# DK-PM-FV-VC-Buck_NonIsolated_V1_0.net
KiCad netlist of a schematic drawn in Altium Designer
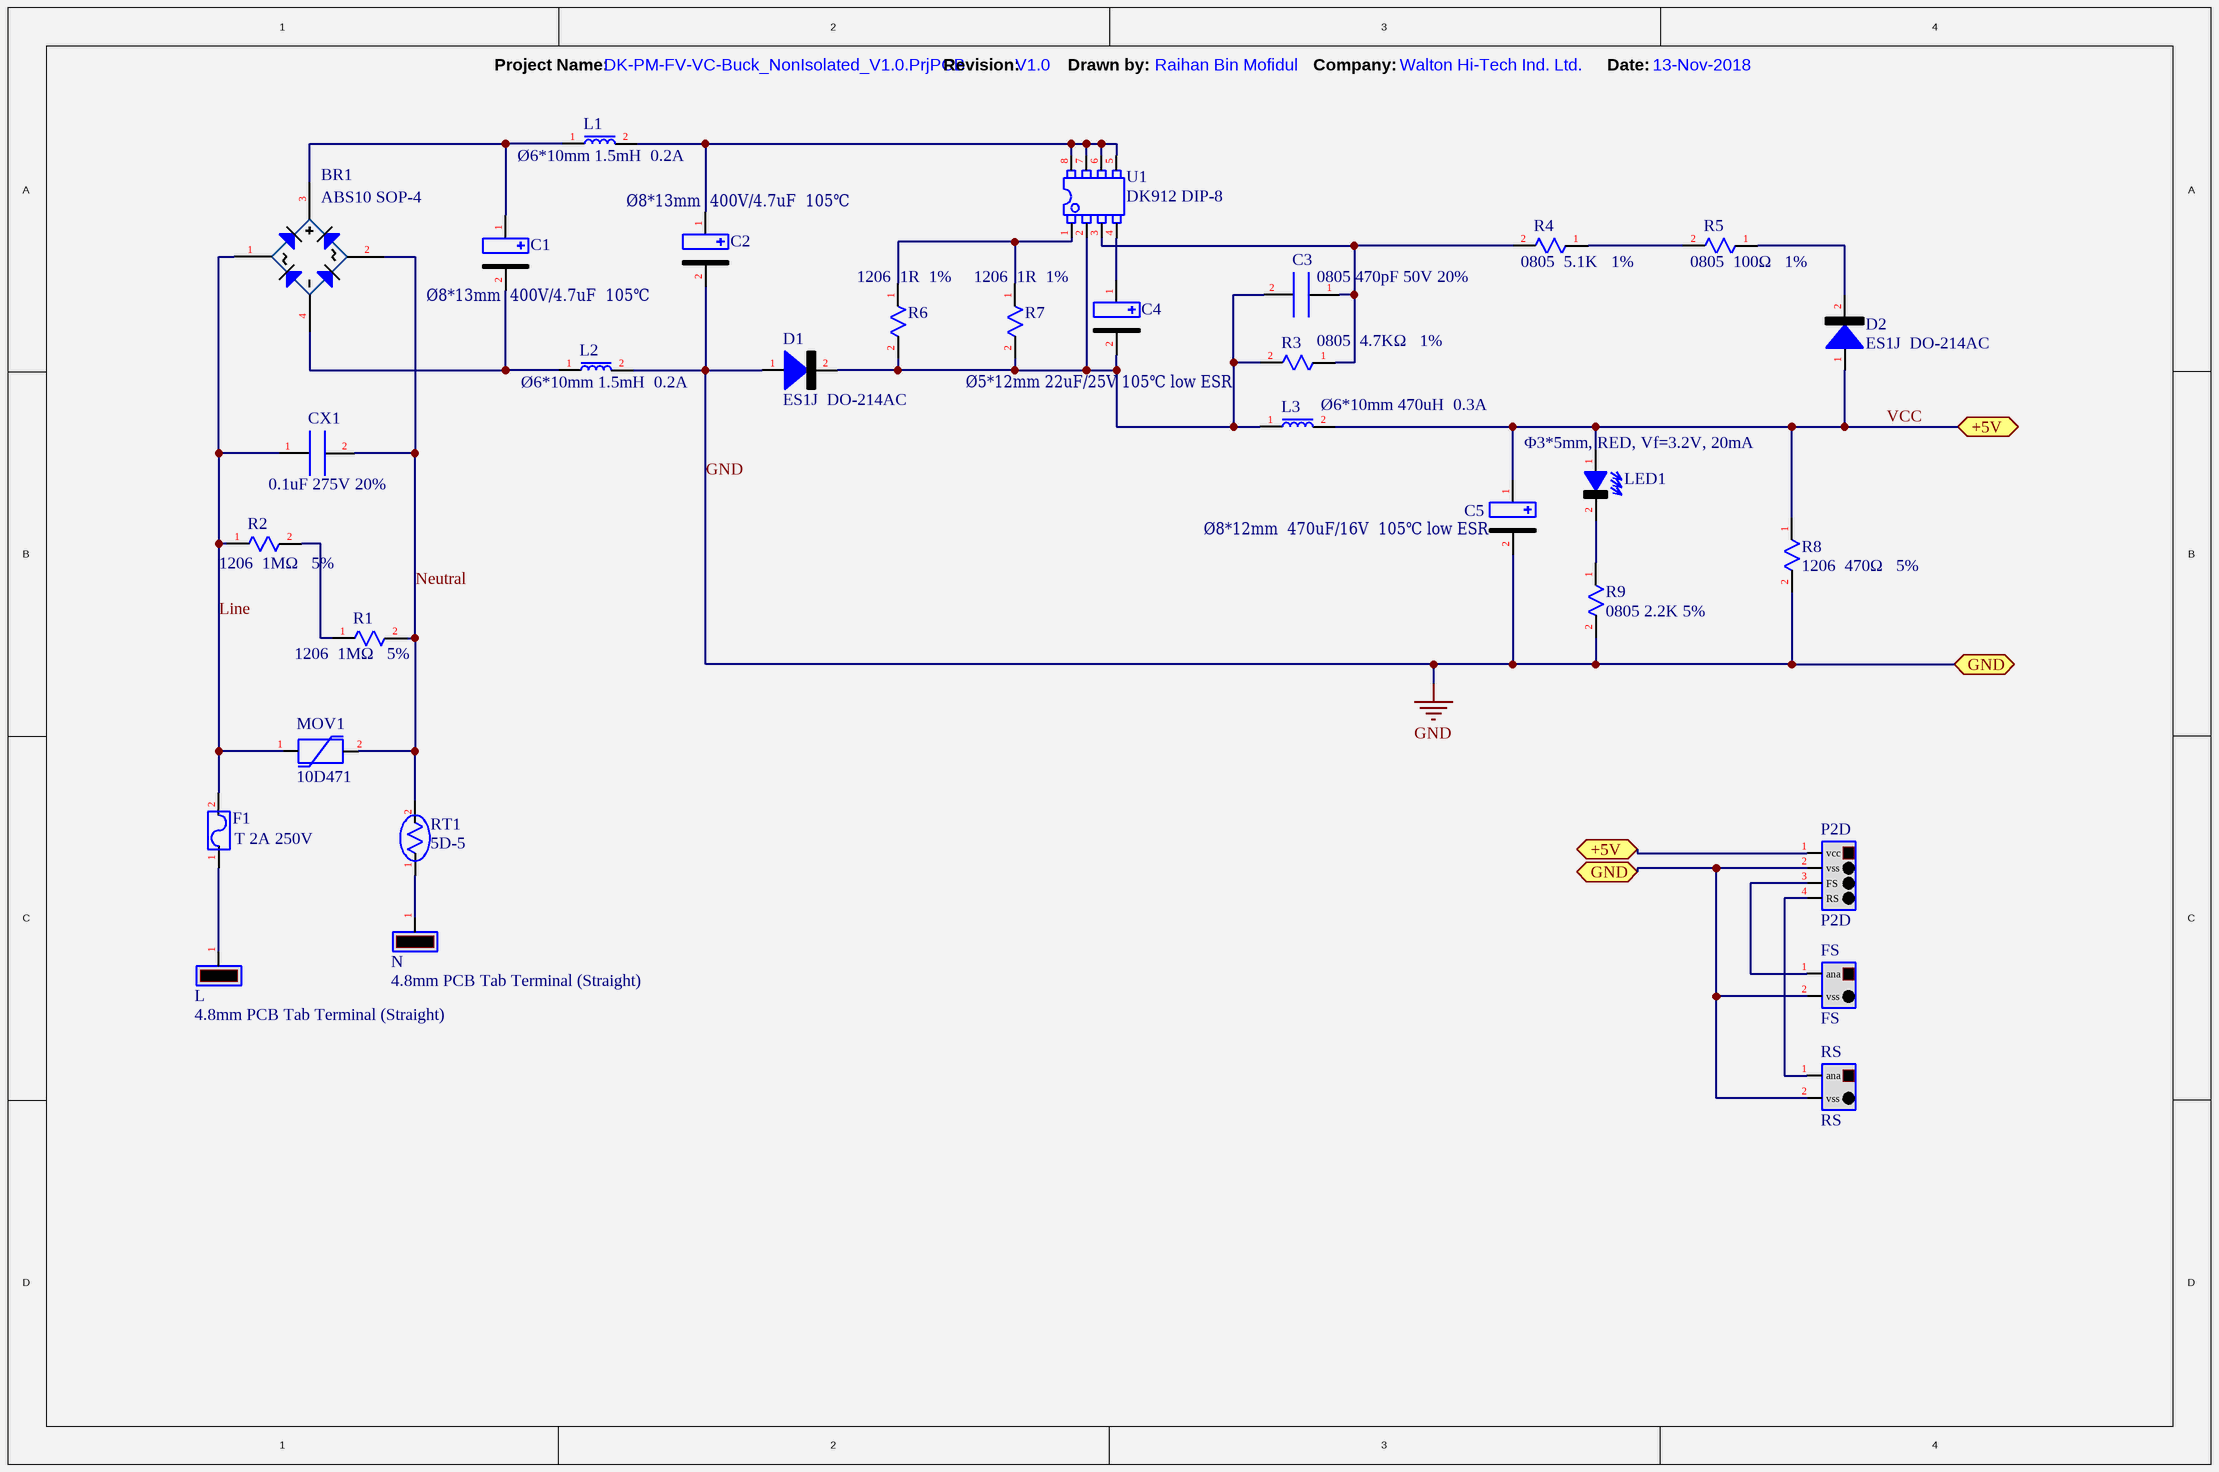
[diagram p0: DK-PM-FV-VC-Buck_NonIsolated_V1.0.SchDoc]

(export (version "E")
  (design (tool "Eeschema 10.0.6"))
  (components
    (comp (ref "BR1")
      (value "ABS10 SOP-4")
      (footprint "BR_SMD_ABS10")
      (libsource (lib "RBM_V1.0_Schlib") (part "Bridge Rectifier"))
    )
    (comp (ref "C1")
      (value "Ø8*13mm  400V/4.7uF  105℃")
      (footprint "C_8x13_P3.556")
      (libsource (lib "RBM_V1.0_Schlib") (part "Capacitor Polar"))
    )
    (comp (ref "C2")
      (value "Ø8*13mm  400V/4.7uF  105℃")
      (footprint "C_8x13_P3.556")
      (libsource (lib "RBM_V1.0_Schlib") (part "Capacitor Polar"))
    )
    (comp (ref "C3")
      (value "0805 470pF 50V 20%")
      (footprint "C_0805")
      (libsource (lib "RBM_V1.0_Schlib") (part "Capacitor Non-Polar"))
    )
    (comp (ref "C4")
      (value "Ø5*12mm 22uF/25V 105℃ low ESR")
      (footprint "C_5x12_P2.54")
      (libsource (lib "RBM_V1.0_Schlib") (part "Capacitor Polar"))
    )
    (comp (ref "C5")
      (value "Ø8*12mm  470uF/16V  105℃ low ESR")
      (footprint "C_8x12_P3.556")
      (libsource (lib "RBM_V1.0_Schlib") (part "Capacitor Polar"))
    )
    (comp (ref "CX1")
      (value "0.1uF 275V 20%")
      (footprint "C_X1_P10")
      (libsource (lib "RBM_V1.0_Schlib") (part "Capacitor Non-Polar"))
    )
    (comp (ref "D1")
      (value "ES1J  DO-214AC")
      (footprint "D_ES1J-DO-214AC")
      (libsource (lib "RBM_V1.0_Schlib") (part "Diode"))
    )
    (comp (ref "D2")
      (value "ES1J  DO-214AC")
      (footprint "D_ES1J-DO-214AC")
      (libsource (lib "RBM_V1.0_Schlib") (part "Diode"))
    )
    (comp (ref "F1")
      (value "T 2A 250V")
      (footprint "F_4x8_P5")
      (libsource (lib "RBM_V1.0_Schlib") (part "Fuse"))
    )
    (comp (ref "FS")
      (value "FS")
      (footprint "CN_B2B-XH-A_RED")
      (libsource (lib "RBM_V1.0_Schlib") (part "Connector_2PINs"))
    )
    (comp (ref "L")
      (value "4.8mm PCB Tab Terminal (Straight)")
      (footprint "CN_4.8mm PCB Tab Terminal (Straight)")
      (libsource (lib "RBM_V1.0_Schlib") (part "Connector_1PIN"))
    )
    (comp (ref "L1")
      (value "Ø6*10mm 1.5mH  0.2A")
      (footprint "L_6x10_P3")
      (libsource (lib "RBM_V1.0_Schlib") (part "Inductor"))
    )
    (comp (ref "L2")
      (value "Ø6*10mm 1.5mH  0.2A")
      (footprint "L_6x10_P3")
      (libsource (lib "RBM_V1.0_Schlib") (part "Inductor"))
    )
    (comp (ref "L3")
      (value "Ø6*10mm 470uH  0.3A")
      (footprint "L_6x10_P3")
      (libsource (lib "RBM_V1.0_Schlib") (part "Inductor"))
    )
    (comp (ref "LED1")
      (value "Φ3*5mm, RED, Vf=3.2V, 20mA")
      (footprint "LED_3x5_P2.5")
      (libsource (lib "RBM_V1.0_Schlib") (part "LED"))
    )
    (comp (ref "MOV1")
      (value "10D471")
      (footprint "MOV_10D471")
      (libsource (lib "RBM_V1.0_Schlib") (part "Varistor"))
    )
    (comp (ref "N")
      (value "4.8mm PCB Tab Terminal (Straight)")
      (footprint "CN_4.8mm PCB Tab Terminal (Straight)")
      (libsource (lib "RBM_V1.0_Schlib") (part "Connector_1PIN"))
    )
    (comp (ref "P2D")
      (value "P2D")
      (footprint "CN_BM04B-GHS-TBT_180_DIP")
      (libsource (lib "RBM_V1.0_Schlib") (part "Connector_4PINs"))
    )
    (comp (ref "R1")
      (value "1206  1MΩ   5%")
      (footprint "R_1206")
      (libsource (lib "RBM_V1.0_Schlib") (part "Resistor"))
    )
    (comp (ref "R2")
      (value "1206  1MΩ   5%")
      (footprint "R_1206")
      (libsource (lib "RBM_V1.0_Schlib") (part "Resistor"))
    )
    (comp (ref "R3")
      (value "0805  4.7KΩ   1%")
      (footprint "R_0805")
      (libsource (lib "RBM_V1.0_Schlib") (part "Resistor"))
    )
    (comp (ref "R4")
      (value "0805  5.1K   1%")
      (footprint "R_0805")
      (libsource (lib "RBM_V1.0_Schlib") (part "Resistor"))
    )
    (comp (ref "R5")
      (value "0805  100Ω   1%")
      (footprint "R_0805")
      (libsource (lib "RBM_V1.0_Schlib") (part "Resistor"))
    )
    (comp (ref "R6")
      (value "1206  1R  1%")
      (footprint "R_1206")
      (libsource (lib "RBM_V1.0_Schlib") (part "Resistor"))
    )
    (comp (ref "R7")
      (value "1206  1R  1%")
      (footprint "R_1206")
      (libsource (lib "RBM_V1.0_Schlib") (part "Resistor"))
    )
    (comp (ref "R8")
      (value "1206  470Ω   5%")
      (footprint "R_1206")
      (libsource (lib "RBM_V1.0_Schlib") (part "Resistor"))
    )
    (comp (ref "R9")
      (value "0805 2.2K 5%")
      (footprint "R_0805")
      (libsource (lib "RBM_V1.0_Schlib") (part "Resistor"))
    )
    (comp (ref "RS")
      (value "RS")
      (footprint "CN_B2B-XH-A_WHITE")
      (libsource (lib "RBM_V1.0_Schlib") (part "Connector_2PINs"))
    )
    (comp (ref "RT1")
      (value "5D-5")
      (footprint "RT_5D-5-(B)")
      (libsource (lib "RBM_V1.0_Schlib") (part "Thermistor"))
    )
    (comp (ref "U1")
      (value "DK912 DIP-8")
      (footprint "U_DK912_TH")
      (libsource (lib "RBM_V1.0_Schlib") (part "IC_SMPS_8pin"))
    )
  )
  (nets
    (net (code "1") (name "/Line") (class "Default")
      (node (ref "BR1") (pin "1") (pinfunction "AC_1") (pintype "passive"))
      (node (ref "CX1") (pin "1") (pinfunction "1_1") (pintype "passive"))
      (node (ref "F1") (pin "2") (pinfunction "2_2") (pintype "passive"))
      (node (ref "MOV1") (pin "1") (pinfunction "1_1") (pintype "passive"))
      (node (ref "R2") (pin "1") (pinfunction "1_1") (pintype "passive"))
    )
    (net (code "2") (name "/Neutral") (class "Default")
      (node (ref "BR1") (pin "2") (pinfunction "AC_2") (pintype "passive"))
      (node (ref "CX1") (pin "2") (pinfunction "2_2") (pintype "passive"))
      (node (ref "MOV1") (pin "2") (pinfunction "2_2") (pintype "passive"))
      (node (ref "R1") (pin "2") (pinfunction "2_2") (pintype "passive"))
      (node (ref "RT1") (pin "2") (pinfunction "2_2") (pintype "passive"))
    )
    (net (code "3") (name "/VCC") (class "Default")
      (node (ref "C5") (pin "1") (pinfunction "vdd_1") (pintype "passive"))
      (node (ref "D2") (pin "1") (pinfunction "vdd_1") (pintype "passive"))
      (node (ref "L3") (pin "2") (pinfunction "2_2") (pintype "passive"))
      (node (ref "LED1") (pin "1") (pinfunction "vdd_1") (pintype "passive"))
      (node (ref "P2D") (pin "1") (pinfunction "vcc_1") (pintype "passive"))
      (node (ref "R8") (pin "1") (pinfunction "1_1") (pintype "passive"))
    )
    (net (code "4") (name "GND") (class "Default")
      (node (ref "C2") (pin "2") (pinfunction "vss_2") (pintype "passive"))
      (node (ref "C5") (pin "2") (pinfunction "vss_2") (pintype "passive"))
      (node (ref "D1") (pin "1") (pinfunction "vdd_1") (pintype "passive"))
      (node (ref "FS") (pin "2") (pinfunction "vss_2") (pintype "passive"))
      (node (ref "L2") (pin "2") (pinfunction "2_2") (pintype "passive"))
      (node (ref "P2D") (pin "2") (pinfunction "vss_2") (pintype "passive"))
      (node (ref "R8") (pin "2") (pinfunction "2_2") (pintype "passive"))
      (node (ref "R9") (pin "2") (pinfunction "2_2") (pintype "passive"))
      (node (ref "RS") (pin "2") (pinfunction "vss_2") (pintype "passive"))
    )
    (net (code "5") (name "Net-(BR1-VCC)") (class "Default")
      (node (ref "BR1") (pin "3") (pinfunction "VCC_3") (pintype "passive"))
      (node (ref "C1") (pin "1") (pinfunction "vdd_1") (pintype "passive"))
      (node (ref "L1") (pin "1") (pinfunction "1_1") (pintype "passive"))
    )
    (net (code "6") (name "Net-(BR1-VSS)") (class "Default")
      (node (ref "BR1") (pin "4") (pinfunction "VSS_4") (pintype "passive"))
      (node (ref "C1") (pin "2") (pinfunction "vss_2") (pintype "passive"))
      (node (ref "L2") (pin "1") (pinfunction "1_1") (pintype "passive"))
    )
    (net (code "7") (name "Net-(C2-vdd)") (class "Default")
      (node (ref "C2") (pin "1") (pinfunction "vdd_1") (pintype "passive"))
      (node (ref "L1") (pin "2") (pinfunction "2_2") (pintype "passive"))
      (node (ref "U1") (pin "5") (pinfunction "5_5") (pintype "passive"))
      (node (ref "U1") (pin "6") (pinfunction "6_6") (pintype "passive"))
      (node (ref "U1") (pin "7") (pinfunction "7_7") (pintype "passive"))
      (node (ref "U1") (pin "8") (pinfunction "8_8") (pintype "passive"))
    )
    (net (code "8") (name "Net-(C3-Pad1)") (class "Default")
      (node (ref "C3") (pin "1") (pinfunction "1_1") (pintype "passive"))
      (node (ref "R3") (pin "1") (pinfunction "1_1") (pintype "passive"))
      (node (ref "R4") (pin "2") (pinfunction "2_2") (pintype "passive"))
      (node (ref "U1") (pin "3") (pinfunction "3_3") (pintype "passive"))
    )
    (net (code "9") (name "Net-(C4-vdd)") (class "Default")
      (node (ref "C4") (pin "1") (pinfunction "vdd_1") (pintype "passive"))
      (node (ref "U1") (pin "4") (pinfunction "4_4") (pintype "passive"))
    )
    (net (code "10") (name "Net-(C4-vss)") (class "Default")
      (node (ref "C3") (pin "2") (pinfunction "2_2") (pintype "passive"))
      (node (ref "C4") (pin "2") (pinfunction "vss_2") (pintype "passive"))
      (node (ref "D1") (pin "2") (pinfunction "vss_2") (pintype "passive"))
      (node (ref "L3") (pin "1") (pinfunction "1_1") (pintype "passive"))
      (node (ref "R3") (pin "2") (pinfunction "2_2") (pintype "passive"))
      (node (ref "R6") (pin "2") (pinfunction "2_2") (pintype "passive"))
      (node (ref "R7") (pin "2") (pinfunction "2_2") (pintype "passive"))
      (node (ref "U1") (pin "2") (pinfunction "2_2") (pintype "passive"))
    )
    (net (code "11") (name "Net-(D2-vss)") (class "Default")
      (node (ref "D2") (pin "2") (pinfunction "vss_2") (pintype "passive"))
      (node (ref "R5") (pin "1") (pinfunction "1_1") (pintype "passive"))
    )
    (net (code "12") (name "Net-(F1-Pad1)") (class "Default")
      (node (ref "F1") (pin "1") (pinfunction "1_1") (pintype "passive"))
      (node (ref "L") (pin "1") (pinfunction "1_1") (pintype "passive"))
    )
    (net (code "13") (name "Net-(FS-ana)") (class "Default")
      (node (ref "FS") (pin "1") (pinfunction "ana_1") (pintype "passive"))
      (node (ref "P2D") (pin "3") (pinfunction "FS_3") (pintype "passive"))
    )
    (net (code "14") (name "Net-(LED1-vss)") (class "Default")
      (node (ref "LED1") (pin "2") (pinfunction "vss_2") (pintype "passive"))
      (node (ref "R9") (pin "1") (pinfunction "1_1") (pintype "passive"))
    )
    (net (code "15") (name "Net-(N-Pad1)") (class "Default")
      (node (ref "N") (pin "1") (pinfunction "1_1") (pintype "passive"))
      (node (ref "RT1") (pin "1") (pinfunction "1_1") (pintype "passive"))
    )
    (net (code "16") (name "Net-(P2D-RS)") (class "Default")
      (node (ref "P2D") (pin "4") (pinfunction "RS_4") (pintype "passive"))
      (node (ref "RS") (pin "1") (pinfunction "ana_1") (pintype "passive"))
    )
    (net (code "17") (name "Net-(R1-Pad1)") (class "Default")
      (node (ref "R1") (pin "1") (pinfunction "1_1") (pintype "passive"))
      (node (ref "R2") (pin "2") (pinfunction "2_2") (pintype "passive"))
    )
    (net (code "18") (name "Net-(R4-Pad1)") (class "Default")
      (node (ref "R4") (pin "1") (pinfunction "1_1") (pintype "passive"))
      (node (ref "R5") (pin "2") (pinfunction "2_2") (pintype "passive"))
    )
    (net (code "19") (name "Net-(R6-Pad1)") (class "Default")
      (node (ref "R6") (pin "1") (pinfunction "1_1") (pintype "passive"))
      (node (ref "R7") (pin "1") (pinfunction "1_1") (pintype "passive"))
      (node (ref "U1") (pin "1") (pinfunction "1_1") (pintype "passive"))
    )
  )
)
